# Sensor.net
KiCad netlist of a schematic drawn in EAGLE
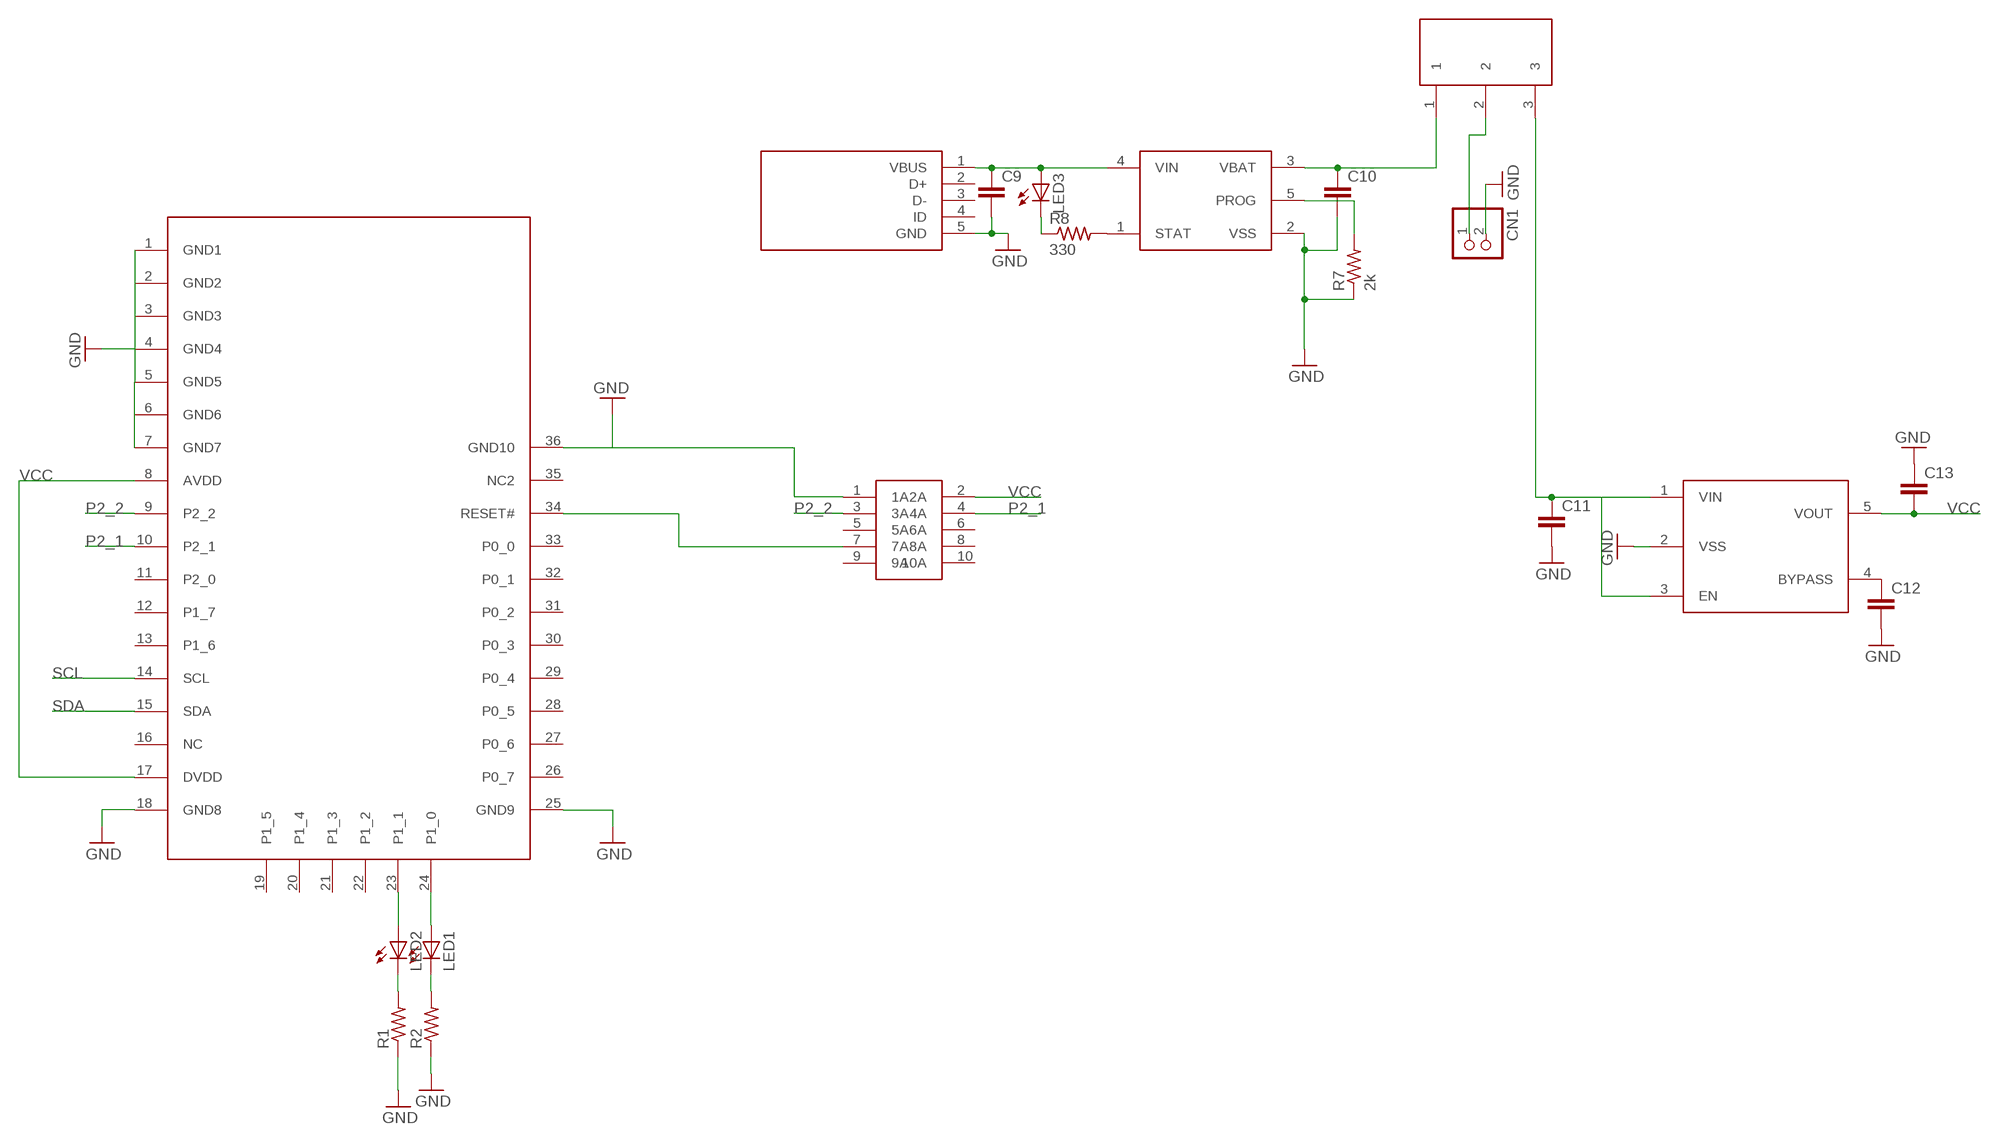
[diagram p0: schematic, sheet 1]
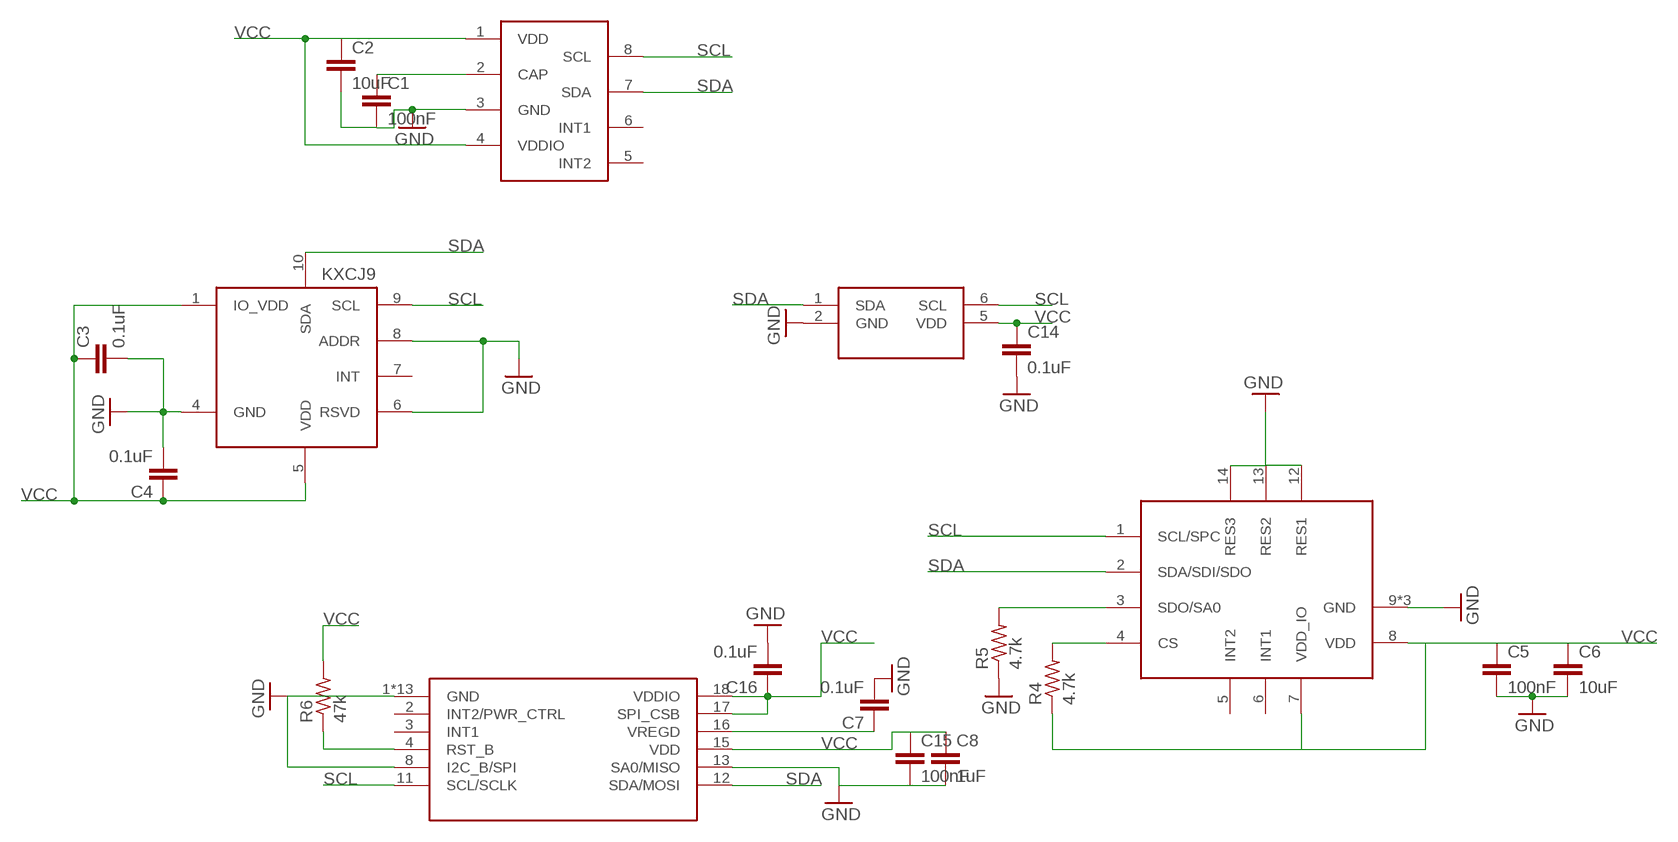
[diagram p1: schematic, sheet 2]

(export (version "E")
  (design (tool "Eeschema 10.0.6"))
  (components
    (comp (ref "C9")
      (value "C-EUC0402")
      (footprint "eagle-import:C0402")
      (libsource (lib "eagle-import") (part "C-EUC0402"))
    )
    (comp (ref "C10")
      (value "C-EUC0402")
      (footprint "eagle-import:C0402")
      (libsource (lib "eagle-import") (part "C-EUC0402"))
    )
    (comp (ref "C11")
      (value "C-EUC0402")
      (footprint "eagle-import:C0402")
      (libsource (lib "eagle-import") (part "C-EUC0402"))
    )
    (comp (ref "C12")
      (value "C-EUC0402")
      (footprint "eagle-import:C0402")
      (libsource (lib "eagle-import") (part "C-EUC0402"))
    )
    (comp (ref "C13")
      (value "C-EUC0402")
      (footprint "eagle-import:C0402")
      (libsource (lib "eagle-import") (part "C-EUC0402"))
    )
    (comp (ref "CN1")
      (value "JST_2PIN-THM")
      (footprint "eagle-import:JST-PH-2-THM")
      (libsource (lib "eagle-import") (part "JST_2PIN-THM"))
    )
    (comp (ref "LED1")
      (value "LEDCHIP-LED0805")
      (footprint "eagle-import:CHIP-LED0805")
      (libsource (lib "eagle-import") (part "LEDCHIP-LED0805"))
    )
    (comp (ref "LED2")
      (value "LEDCHIP-LED0805")
      (footprint "eagle-import:CHIP-LED0805")
      (libsource (lib "eagle-import") (part "LEDCHIP-LED0805"))
    )
    (comp (ref "LED3")
      (value "LEDCHIP-LED0805")
      (footprint "eagle-import:CHIP-LED0805")
      (libsource (lib "eagle-import") (part "LEDCHIP-LED0805"))
    )
    (comp (ref "R1")
      (value "R-US_R0402")
      (footprint "eagle-import:R0402")
      (libsource (lib "eagle-import") (part "R-US_R0402"))
    )
    (comp (ref "R2")
      (value "R-US_R0402")
      (footprint "eagle-import:R0402")
      (libsource (lib "eagle-import") (part "R-US_R0402"))
    )
    (comp (ref "R7")
      (value "2k")
      (footprint "eagle-import:R0402")
      (libsource (lib "eagle-import") (part "R-US_R0402"))
    )
    (comp (ref "R8")
      (value "330")
      (footprint "eagle-import:R0402")
      (libsource (lib "eagle-import") (part "R-US_R0402"))
    )
    (comp (ref "U$1")
      (value "BLE113")
      (footprint "eagle-import:BLUEGIGA")
      (libsource (lib "eagle-import") (part "BLE113"))
    )
    (comp (ref "U$2")
      (value "MCP73831")
      (footprint "eagle-import:SOT23-5L")
      (libsource (lib "eagle-import") (part "MCP73831"))
    )
    (comp (ref "U$8")
      (value "RIBBON_10POS_MALE")
      (footprint "eagle-import:RIBBON_10POS_MALE")
      (libsource (lib "eagle-import") (part "RIBBON_10POS_MALE"))
    )
    (comp (ref "U$9")
      (value "SPDT_THRU")
      (footprint "eagle-import:SPDT_THRU")
      (libsource (lib "eagle-import") (part "SPDT_THRU"))
    )
    (comp (ref "U$10")
      (value "USB_MINI")
      (footprint "eagle-import:USB_MINI")
      (libsource (lib "eagle-import") (part "USB_MINI"))
    )
    (comp (ref "U$11")
      (value "LP3985")
      (footprint "eagle-import:SOT23-5L")
      (libsource (lib "eagle-import") (part "LP3985"))
    )
    (comp (ref "ACCEL_16")
      (value "LISDH_16G")
      (footprint "eagle-import:LGA14_2X2")
      (libsource (lib "eagle-import") (part "LISDH_16G"))
    )
    (comp (ref "C1")
      (value "100nF")
      (footprint "eagle-import:C0402")
      (libsource (lib "eagle-import") (part "C-EUC0402"))
    )
    (comp (ref "C2")
      (value "10uF")
      (footprint "eagle-import:C0402")
      (libsource (lib "eagle-import") (part "C-EUC0402"))
    )
    (comp (ref "C3")
      (value "0.1uF")
      (footprint "eagle-import:C0402")
      (libsource (lib "eagle-import") (part "C-EUC0402"))
    )
    (comp (ref "C4")
      (value "0.1uF")
      (footprint "eagle-import:C0402")
      (libsource (lib "eagle-import") (part "C-EUC0402"))
    )
    (comp (ref "C5")
      (value "100nF")
      (footprint "eagle-import:C0402")
      (libsource (lib "eagle-import") (part "C-EUC0402"))
    )
    (comp (ref "C6")
      (value "10uF")
      (footprint "eagle-import:C0402")
      (libsource (lib "eagle-import") (part "C-EUC0402"))
    )
    (comp (ref "C7")
      (value "0.1uF")
      (footprint "eagle-import:C0402")
      (libsource (lib "eagle-import") (part "C-EUC0402"))
    )
    (comp (ref "C8")
      (value "1uF")
      (footprint "eagle-import:C0402")
      (libsource (lib "eagle-import") (part "C-EUC0402"))
    )
    (comp (ref "C14")
      (value "0.1uF")
      (footprint "eagle-import:C0402")
      (libsource (lib "eagle-import") (part "C-EUC0402"))
    )
    (comp (ref "C15")
      (value "100nF")
      (footprint "eagle-import:C0402")
      (libsource (lib "eagle-import") (part "C-EUC0402"))
    )
    (comp (ref "C16")
      (value "0.1uF")
      (footprint "eagle-import:C0402")
      (libsource (lib "eagle-import") (part "C-EUC0402"))
    )
    (comp (ref "R4")
      (value "4.7k")
      (footprint "eagle-import:R0402")
      (libsource (lib "eagle-import") (part "R-US_R0402"))
    )
    (comp (ref "R5")
      (value "4.7k")
      (footprint "eagle-import:R0402")
      (libsource (lib "eagle-import") (part "R-US_R0402"))
    )
    (comp (ref "R6")
      (value "47k")
      (footprint "eagle-import:R0402")
      (libsource (lib "eagle-import") (part "R-US_R0402"))
    )
    (comp (ref "U$12")
      (value "KXCJ9")
      (footprint "eagle-import:KXCJ9")
      (libsource (lib "eagle-import") (part "KXCJ9"))
    )
    (comp (ref "U$13")
      (value "MLP3115A2")
      (footprint "eagle-import:MLP3115A2")
      (libsource (lib "eagle-import") (part "MLP3115A2"))
    )
    (comp (ref "U$14")
      (value "FXAS21002")
      (footprint "eagle-import:FXAS21002")
      (libsource (lib "eagle-import") (part "FXAS21002"))
    )
    (comp (ref "U$15")
      (value "SI7021-A20")
      (footprint "eagle-import:SI7021-A20")
      (libsource (lib "eagle-import") (part "SI7021-A20"))
    )
  )
  (nets
    (net (code "1") (name "GND") (class "Default")
      (node (ref "ACCEL_16") (pin "10") (pinfunction "GND_10") (pintype "bidirectional"))
      (node (ref "ACCEL_16") (pin "11") (pinfunction "GND_11") (pintype "bidirectional"))
      (node (ref "ACCEL_16") (pin "12") (pinfunction "RES1_12") (pintype "bidirectional"))
      (node (ref "ACCEL_16") (pin "13") (pinfunction "RES2_13") (pintype "bidirectional"))
      (node (ref "ACCEL_16") (pin "14") (pinfunction "RES3_14") (pintype "bidirectional"))
      (node (ref "ACCEL_16") (pin "9") (pinfunction "GND_9") (pintype "bidirectional"))
      (node (ref "C1") (pin "2") (pinfunction "2_2") (pintype "passive"))
      (node (ref "C10") (pin "2") (pinfunction "2_2") (pintype "passive"))
      (node (ref "C11") (pin "2") (pinfunction "2_2") (pintype "passive"))
      (node (ref "C12") (pin "2") (pinfunction "2_2") (pintype "passive"))
      (node (ref "C13") (pin "1") (pinfunction "1_1") (pintype "passive"))
      (node (ref "C14") (pin "2") (pinfunction "2_2") (pintype "passive"))
      (node (ref "C15") (pin "2") (pinfunction "2_2") (pintype "passive"))
      (node (ref "C16") (pin "2") (pinfunction "2_2") (pintype "passive"))
      (node (ref "C2") (pin "2") (pinfunction "2_2") (pintype "passive"))
      (node (ref "C3") (pin "2") (pinfunction "2_2") (pintype "passive"))
      (node (ref "C4") (pin "2") (pinfunction "2_2") (pintype "passive"))
      (node (ref "C5") (pin "2") (pinfunction "2_2") (pintype "passive"))
      (node (ref "C6") (pin "2") (pinfunction "2_2") (pintype "passive"))
      (node (ref "C7") (pin "2") (pinfunction "2_2") (pintype "passive"))
      (node (ref "C8") (pin "2") (pinfunction "2_2") (pintype "passive"))
      (node (ref "C9") (pin "2") (pinfunction "2_2") (pintype "passive"))
      (node (ref "CN1") (pin "2") (pinfunction "1_2") (pintype "passive"))
      (node (ref "R1") (pin "1") (pinfunction "1_1") (pintype "passive"))
      (node (ref "R2") (pin "1") (pinfunction "1_1") (pintype "passive"))
      (node (ref "R5") (pin "1") (pinfunction "1_1") (pintype "passive"))
      (node (ref "R7") (pin "1") (pinfunction "1_1") (pintype "passive"))
      (node (ref "U$1") (pin "1") (pinfunction "GND1_1") (pintype "bidirectional"))
      (node (ref "U$1") (pin "18") (pinfunction "GND8_18") (pintype "bidirectional"))
      (node (ref "U$1") (pin "2") (pinfunction "GND2_2") (pintype "bidirectional"))
      (node (ref "U$1") (pin "25") (pinfunction "GND9_25") (pintype "bidirectional"))
      (node (ref "U$1") (pin "3") (pinfunction "GND3_3") (pintype "bidirectional"))
      (node (ref "U$1") (pin "36") (pinfunction "GND10_36") (pintype "bidirectional"))
      (node (ref "U$1") (pin "4") (pinfunction "GND4_4") (pintype "bidirectional"))
      (node (ref "U$1") (pin "5") (pinfunction "GND5_5") (pintype "bidirectional"))
      (node (ref "U$1") (pin "6") (pinfunction "GND6_6") (pintype "bidirectional"))
      (node (ref "U$1") (pin "7") (pinfunction "GND7_7") (pintype "bidirectional"))
      (node (ref "U$10") (pin "5") (pinfunction "GND_5") (pintype "bidirectional"))
      (node (ref "U$11") (pin "2") (pinfunction "VSS_2") (pintype "bidirectional"))
      (node (ref "U$12") (pin "4") (pinfunction "GND_4") (pintype "bidirectional"))
      (node (ref "U$12") (pin "6") (pinfunction "RSVD_6") (pintype "bidirectional"))
      (node (ref "U$12") (pin "8") (pinfunction "ADDR_8") (pintype "bidirectional"))
      (node (ref "U$13") (pin "3") (pinfunction "GND_3") (pintype "bidirectional"))
      (node (ref "U$14") (pin "1") (pinfunction "GND_1") (pintype "bidirectional"))
      (node (ref "U$14") (pin "10") (pinfunction "GND_10") (pintype "bidirectional"))
      (node (ref "U$14") (pin "13") (pinfunction "SA0/MISO_13") (pintype "bidirectional"))
      (node (ref "U$14") (pin "14") (pinfunction "GND_14") (pintype "bidirectional"))
      (node (ref "U$14") (pin "19") (pinfunction "GND_19") (pintype "bidirectional"))
      (node (ref "U$14") (pin "20") (pinfunction "GND_20") (pintype "bidirectional"))
      (node (ref "U$14") (pin "21") (pinfunction "GND_21") (pintype "bidirectional"))
      (node (ref "U$14") (pin "22") (pinfunction "GND_22") (pintype "bidirectional"))
      (node (ref "U$14") (pin "23") (pinfunction "GND_23") (pintype "bidirectional"))
      (node (ref "U$14") (pin "24") (pinfunction "GND_24") (pintype "bidirectional"))
      (node (ref "U$14") (pin "5") (pinfunction "GND_5") (pintype "bidirectional"))
      (node (ref "U$14") (pin "6") (pinfunction "GND_6") (pintype "bidirectional"))
      (node (ref "U$14") (pin "7") (pinfunction "GND_7") (pintype "bidirectional"))
      (node (ref "U$14") (pin "8") (pinfunction "I2C_B/SPI_8") (pintype "bidirectional"))
      (node (ref "U$14") (pin "9") (pinfunction "GND_9") (pintype "bidirectional"))
      (node (ref "U$15") (pin "2") (pinfunction "GND_2") (pintype "bidirectional"))
      (node (ref "U$2") (pin "2") (pinfunction "VSS_2") (pintype "bidirectional"))
      (node (ref "U$8") (pin "1") (pinfunction "1A_1") (pintype "bidirectional"))
    )
    (net (code "2") (name "Net-(ACCEL_16-CS)") (class "Default")
      (node (ref "ACCEL_16") (pin "4") (pinfunction "CS_4") (pintype "bidirectional"))
      (node (ref "R4") (pin "2") (pinfunction "2_2") (pintype "passive"))
    )
    (net (code "3") (name "Net-(ACCEL_16-SDO{slash}SA0)") (class "Default")
      (node (ref "ACCEL_16") (pin "3") (pinfunction "SDO/SA0_3") (pintype "bidirectional"))
      (node (ref "R5") (pin "2") (pinfunction "2_2") (pintype "passive"))
    )
    (net (code "4") (name "Net-(CN1-2)") (class "Default")
      (node (ref "CN1") (pin "1") (pinfunction "2_1") (pintype "passive"))
      (node (ref "U$9") (pin "2") (pinfunction "2_2") (pintype "bidirectional"))
    )
    (net (code "5") (name "Net-(LED1-PadC)") (class "Default")
      (node (ref "LED1") (pin "C") (pinfunction "C_C") (pintype "passive"))
      (node (ref "R2") (pin "2") (pinfunction "2_2") (pintype "passive"))
    )
    (net (code "6") (name "Net-(LED2-PadC)") (class "Default")
      (node (ref "LED2") (pin "C") (pinfunction "C_C") (pintype "passive"))
      (node (ref "R1") (pin "2") (pinfunction "2_2") (pintype "passive"))
    )
    (net (code "7") (name "Net-(LED3-PadC)") (class "Default")
      (node (ref "LED3") (pin "C") (pinfunction "C_C") (pintype "passive"))
      (node (ref "R8") (pin "1") (pinfunction "1_1") (pintype "passive"))
    )
    (net (code "8") (name "Net-(U$1-P1_0)") (class "Default")
      (node (ref "LED1") (pin "A") (pinfunction "A_A") (pintype "passive"))
      (node (ref "U$1") (pin "24") (pinfunction "P1_0_24") (pintype "bidirectional"))
    )
    (net (code "9") (name "Net-(U$1-P1_1)") (class "Default")
      (node (ref "LED2") (pin "A") (pinfunction "A_A") (pintype "passive"))
      (node (ref "U$1") (pin "23") (pinfunction "P1_1_23") (pintype "bidirectional"))
    )
    (net (code "10") (name "Net-(U$1-RESET#)") (class "Default")
      (node (ref "U$1") (pin "34") (pinfunction "RESET#_34") (pintype "bidirectional"))
      (node (ref "U$8") (pin "7") (pinfunction "7A_7") (pintype "bidirectional"))
    )
    (net (code "11") (name "Net-(U$2-PROG)") (class "Default")
      (node (ref "R7") (pin "2") (pinfunction "2_2") (pintype "passive"))
      (node (ref "U$2") (pin "5") (pinfunction "PROG_5") (pintype "bidirectional"))
    )
    (net (code "12") (name "Net-(U$2-STAT)") (class "Default")
      (node (ref "R8") (pin "2") (pinfunction "2_2") (pintype "passive"))
      (node (ref "U$2") (pin "1") (pinfunction "STAT_1") (pintype "bidirectional"))
    )
    (net (code "13") (name "Net-(U$2-VBAT)") (class "Default")
      (node (ref "C10") (pin "1") (pinfunction "1_1") (pintype "passive"))
      (node (ref "U$2") (pin "3") (pinfunction "VBAT_3") (pintype "bidirectional"))
      (node (ref "U$9") (pin "1") (pinfunction "1_1") (pintype "bidirectional"))
    )
    (net (code "14") (name "Net-(U$10-VBUS)") (class "Default")
      (node (ref "C9") (pin "1") (pinfunction "1_1") (pintype "passive"))
      (node (ref "LED3") (pin "A") (pinfunction "A_A") (pintype "passive"))
      (node (ref "U$10") (pin "1") (pinfunction "VBUS_1") (pintype "bidirectional"))
      (node (ref "U$2") (pin "4") (pinfunction "VIN_4") (pintype "bidirectional"))
    )
    (net (code "15") (name "Net-(U$11-BYPASS)") (class "Default")
      (node (ref "C12") (pin "1") (pinfunction "1_1") (pintype "passive"))
      (node (ref "U$11") (pin "4") (pinfunction "BYPASS_4") (pintype "bidirectional"))
    )
    (net (code "16") (name "Net-(U$11-EN)") (class "Default")
      (node (ref "C11") (pin "1") (pinfunction "1_1") (pintype "passive"))
      (node (ref "U$11") (pin "1") (pinfunction "VIN_1") (pintype "bidirectional"))
      (node (ref "U$11") (pin "3") (pinfunction "EN_3") (pintype "bidirectional"))
      (node (ref "U$9") (pin "3") (pinfunction "3_3") (pintype "bidirectional"))
    )
    (net (code "17") (name "Net-(U$13-CAP)") (class "Default")
      (node (ref "C1") (pin "1") (pinfunction "1_1") (pintype "passive"))
      (node (ref "U$13") (pin "2") (pinfunction "CAP_2") (pintype "bidirectional"))
    )
    (net (code "18") (name "Net-(U$14-RST_B)") (class "Default")
      (node (ref "R6") (pin "1") (pinfunction "1_1") (pintype "passive"))
      (node (ref "U$14") (pin "4") (pinfunction "RST_B_4") (pintype "bidirectional"))
    )
    (net (code "19") (name "Net-(U$14-VREGD)") (class "Default")
      (node (ref "C7") (pin "1") (pinfunction "1_1") (pintype "passive"))
      (node (ref "U$14") (pin "16") (pinfunction "VREGD_16") (pintype "bidirectional"))
    )
    (net (code "20") (name "P2_1") (class "Default")
      (node (ref "U$1") (pin "10") (pinfunction "P2_1_10") (pintype "bidirectional"))
      (node (ref "U$8") (pin "4") (pinfunction "4A_4") (pintype "bidirectional"))
    )
    (net (code "21") (name "P2_2") (class "Default")
      (node (ref "U$1") (pin "9") (pinfunction "P2_2_9") (pintype "bidirectional"))
      (node (ref "U$8") (pin "3") (pinfunction "3A_3") (pintype "bidirectional"))
    )
    (net (code "22") (name "SCL") (class "Default")
      (node (ref "ACCEL_16") (pin "1") (pinfunction "SCL/SPC_1") (pintype "bidirectional"))
      (node (ref "U$1") (pin "14") (pinfunction "SCL_14") (pintype "bidirectional"))
      (node (ref "U$12") (pin "9") (pinfunction "SCL_9") (pintype "bidirectional"))
      (node (ref "U$13") (pin "8") (pinfunction "SCL_8") (pintype "bidirectional"))
      (node (ref "U$14") (pin "11") (pinfunction "SCL/SCLK_11") (pintype "bidirectional"))
      (node (ref "U$15") (pin "6") (pinfunction "SCL_6") (pintype "bidirectional"))
    )
    (net (code "23") (name "SDA") (class "Default")
      (node (ref "ACCEL_16") (pin "2") (pinfunction "SDA/SDI/SDO_2") (pintype "bidirectional"))
      (node (ref "U$1") (pin "15") (pinfunction "SDA_15") (pintype "bidirectional"))
      (node (ref "U$12") (pin "10") (pinfunction "SDA_10") (pintype "bidirectional"))
      (node (ref "U$13") (pin "7") (pinfunction "SDA_7") (pintype "bidirectional"))
      (node (ref "U$14") (pin "12") (pinfunction "SDA/MOSI_12") (pintype "bidirectional"))
      (node (ref "U$15") (pin "1") (pinfunction "SDA_1") (pintype "bidirectional"))
    )
    (net (code "24") (name "VCC") (class "Default")
      (node (ref "ACCEL_16") (pin "7") (pinfunction "VDD_IO_7") (pintype "bidirectional"))
      (node (ref "ACCEL_16") (pin "8") (pinfunction "VDD_8") (pintype "bidirectional"))
      (node (ref "C13") (pin "2") (pinfunction "2_2") (pintype "passive"))
      (node (ref "C14") (pin "1") (pinfunction "1_1") (pintype "passive"))
      (node (ref "C15") (pin "1") (pinfunction "1_1") (pintype "passive"))
      (node (ref "C16") (pin "1") (pinfunction "1_1") (pintype "passive"))
      (node (ref "C2") (pin "1") (pinfunction "1_1") (pintype "passive"))
      (node (ref "C3") (pin "1") (pinfunction "1_1") (pintype "passive"))
      (node (ref "C4") (pin "1") (pinfunction "1_1") (pintype "passive"))
      (node (ref "C5") (pin "1") (pinfunction "1_1") (pintype "passive"))
      (node (ref "C6") (pin "1") (pinfunction "1_1") (pintype "passive"))
      (node (ref "C8") (pin "1") (pinfunction "1_1") (pintype "passive"))
      (node (ref "R4") (pin "1") (pinfunction "1_1") (pintype "passive"))
      (node (ref "R6") (pin "2") (pinfunction "2_2") (pintype "passive"))
      (node (ref "U$1") (pin "17") (pinfunction "DVDD_17") (pintype "bidirectional"))
      (node (ref "U$1") (pin "8") (pinfunction "AVDD_8") (pintype "bidirectional"))
      (node (ref "U$11") (pin "5") (pinfunction "VOUT_5") (pintype "bidirectional"))
      (node (ref "U$12") (pin "1") (pinfunction "IO_VDD_1") (pintype "bidirectional"))
      (node (ref "U$12") (pin "5") (pinfunction "VDD_5") (pintype "bidirectional"))
      (node (ref "U$13") (pin "1") (pinfunction "VDD_1") (pintype "bidirectional"))
      (node (ref "U$13") (pin "4") (pinfunction "VDDIO_4") (pintype "bidirectional"))
      (node (ref "U$14") (pin "15") (pinfunction "VDD_15") (pintype "bidirectional"))
      (node (ref "U$14") (pin "17") (pinfunction "SPI_CSB_17") (pintype "bidirectional"))
      (node (ref "U$14") (pin "18") (pinfunction "VDDIO_18") (pintype "bidirectional"))
      (node (ref "U$15") (pin "5") (pinfunction "VDD_5") (pintype "bidirectional"))
      (node (ref "U$8") (pin "2") (pinfunction "2A_2") (pintype "bidirectional"))
    )
    (net (code "25") (name "unconnected-(ACCEL_16-INT1-Pad6)") (class "Default")
      (node (ref "ACCEL_16") (pin "6") (pinfunction "INT1_6") (pintype "bidirectional"))
    )
    (net (code "26") (name "unconnected-(ACCEL_16-INT2-Pad5)") (class "Default")
      (node (ref "ACCEL_16") (pin "5") (pinfunction "INT2_5") (pintype "bidirectional"))
    )
    (net (code "27") (name "unconnected-(U$1-NC-Pad16)") (class "Default")
      (node (ref "U$1") (pin "16") (pinfunction "NC_16") (pintype "bidirectional"))
    )
    (net (code "28") (name "unconnected-(U$1-NC2-Pad35)") (class "Default")
      (node (ref "U$1") (pin "35") (pinfunction "NC2_35") (pintype "bidirectional"))
    )
    (net (code "29") (name "unconnected-(U$1-P0_0-Pad33)") (class "Default")
      (node (ref "U$1") (pin "33") (pinfunction "P0_0_33") (pintype "bidirectional"))
    )
    (net (code "30") (name "unconnected-(U$1-P0_1-Pad32)") (class "Default")
      (node (ref "U$1") (pin "32") (pinfunction "P0_1_32") (pintype "bidirectional"))
    )
    (net (code "31") (name "unconnected-(U$1-P0_2-Pad31)") (class "Default")
      (node (ref "U$1") (pin "31") (pinfunction "P0_2_31") (pintype "bidirectional"))
    )
    (net (code "32") (name "unconnected-(U$1-P0_3-Pad30)") (class "Default")
      (node (ref "U$1") (pin "30") (pinfunction "P0_3_30") (pintype "bidirectional"))
    )
    (net (code "33") (name "unconnected-(U$1-P0_4-Pad29)") (class "Default")
      (node (ref "U$1") (pin "29") (pinfunction "P0_4_29") (pintype "bidirectional"))
    )
    (net (code "34") (name "unconnected-(U$1-P0_5-Pad28)") (class "Default")
      (node (ref "U$1") (pin "28") (pinfunction "P0_5_28") (pintype "bidirectional"))
    )
    (net (code "35") (name "unconnected-(U$1-P0_6-Pad27)") (class "Default")
      (node (ref "U$1") (pin "27") (pinfunction "P0_6_27") (pintype "bidirectional"))
    )
    (net (code "36") (name "unconnected-(U$1-P0_7-Pad26)") (class "Default")
      (node (ref "U$1") (pin "26") (pinfunction "P0_7_26") (pintype "bidirectional"))
    )
    (net (code "37") (name "unconnected-(U$1-P1_2-Pad22)") (class "Default")
      (node (ref "U$1") (pin "22") (pinfunction "P1_2_22") (pintype "bidirectional"))
    )
    (net (code "38") (name "unconnected-(U$1-P1_3-Pad21)") (class "Default")
      (node (ref "U$1") (pin "21") (pinfunction "P1_3_21") (pintype "bidirectional"))
    )
    (net (code "39") (name "unconnected-(U$1-P1_4-Pad20)") (class "Default")
      (node (ref "U$1") (pin "20") (pinfunction "P1_4_20") (pintype "bidirectional"))
    )
    (net (code "40") (name "unconnected-(U$1-P1_5-Pad19)") (class "Default")
      (node (ref "U$1") (pin "19") (pinfunction "P1_5_19") (pintype "bidirectional"))
    )
    (net (code "41") (name "unconnected-(U$1-P1_6-Pad13)") (class "Default")
      (node (ref "U$1") (pin "13") (pinfunction "P1_6_13") (pintype "bidirectional"))
    )
    (net (code "42") (name "unconnected-(U$1-P1_7-Pad12)") (class "Default")
      (node (ref "U$1") (pin "12") (pinfunction "P1_7_12") (pintype "bidirectional"))
    )
    (net (code "43") (name "unconnected-(U$1-P2_0-Pad11)") (class "Default")
      (node (ref "U$1") (pin "11") (pinfunction "P2_0_11") (pintype "bidirectional"))
    )
    (net (code "44") (name "unconnected-(U$8-5A-Pad5)") (class "Default")
      (node (ref "U$8") (pin "5") (pinfunction "5A_5") (pintype "bidirectional"))
    )
    (net (code "45") (name "unconnected-(U$8-6A-Pad6)") (class "Default")
      (node (ref "U$8") (pin "6") (pinfunction "6A_6") (pintype "bidirectional"))
    )
    (net (code "46") (name "unconnected-(U$8-8A-Pad8)") (class "Default")
      (node (ref "U$8") (pin "8") (pinfunction "8A_8") (pintype "bidirectional"))
    )
    (net (code "47") (name "unconnected-(U$8-9A-Pad9)") (class "Default")
      (node (ref "U$8") (pin "9") (pinfunction "9A_9") (pintype "bidirectional"))
    )
    (net (code "48") (name "unconnected-(U$8-10A-Pad10)") (class "Default")
      (node (ref "U$8") (pin "10") (pinfunction "10A_10") (pintype "bidirectional"))
    )
    (net (code "49") (name "unconnected-(U$10-D+-Pad2)") (class "Default")
      (node (ref "U$10") (pin "2") (pinfunction "D+_2") (pintype "bidirectional"))
    )
    (net (code "50") (name "unconnected-(U$10-D--Pad3)") (class "Default")
      (node (ref "U$10") (pin "3") (pinfunction "D-_3") (pintype "bidirectional"))
    )
    (net (code "51") (name "unconnected-(U$10-ID-Pad4)") (class "Default")
      (node (ref "U$10") (pin "4") (pinfunction "ID_4") (pintype "bidirectional"))
    )
    (net (code "52") (name "unconnected-(U$12-INT-Pad7)") (class "Default")
      (node (ref "U$12") (pin "7") (pinfunction "INT_7") (pintype "bidirectional"))
    )
    (net (code "53") (name "unconnected-(U$13-INT1-Pad6)") (class "Default")
      (node (ref "U$13") (pin "6") (pinfunction "INT1_6") (pintype "bidirectional"))
    )
    (net (code "54") (name "unconnected-(U$13-INT2-Pad5)") (class "Default")
      (node (ref "U$13") (pin "5") (pinfunction "INT2_5") (pintype "bidirectional"))
    )
    (net (code "55") (name "unconnected-(U$14-INT1-Pad3)") (class "Default")
      (node (ref "U$14") (pin "3") (pinfunction "INT1_3") (pintype "bidirectional"))
    )
    (net (code "56") (name "unconnected-(U$14-INT2{slash}PWR_CTRL-Pad2)") (class "Default")
      (node (ref "U$14") (pin "2") (pinfunction "INT2/PWR_CTRL_2") (pintype "bidirectional"))
    )
  )
)
